# Power-Management.net
KiCad netlist of a schematic drawn in Altium Designer
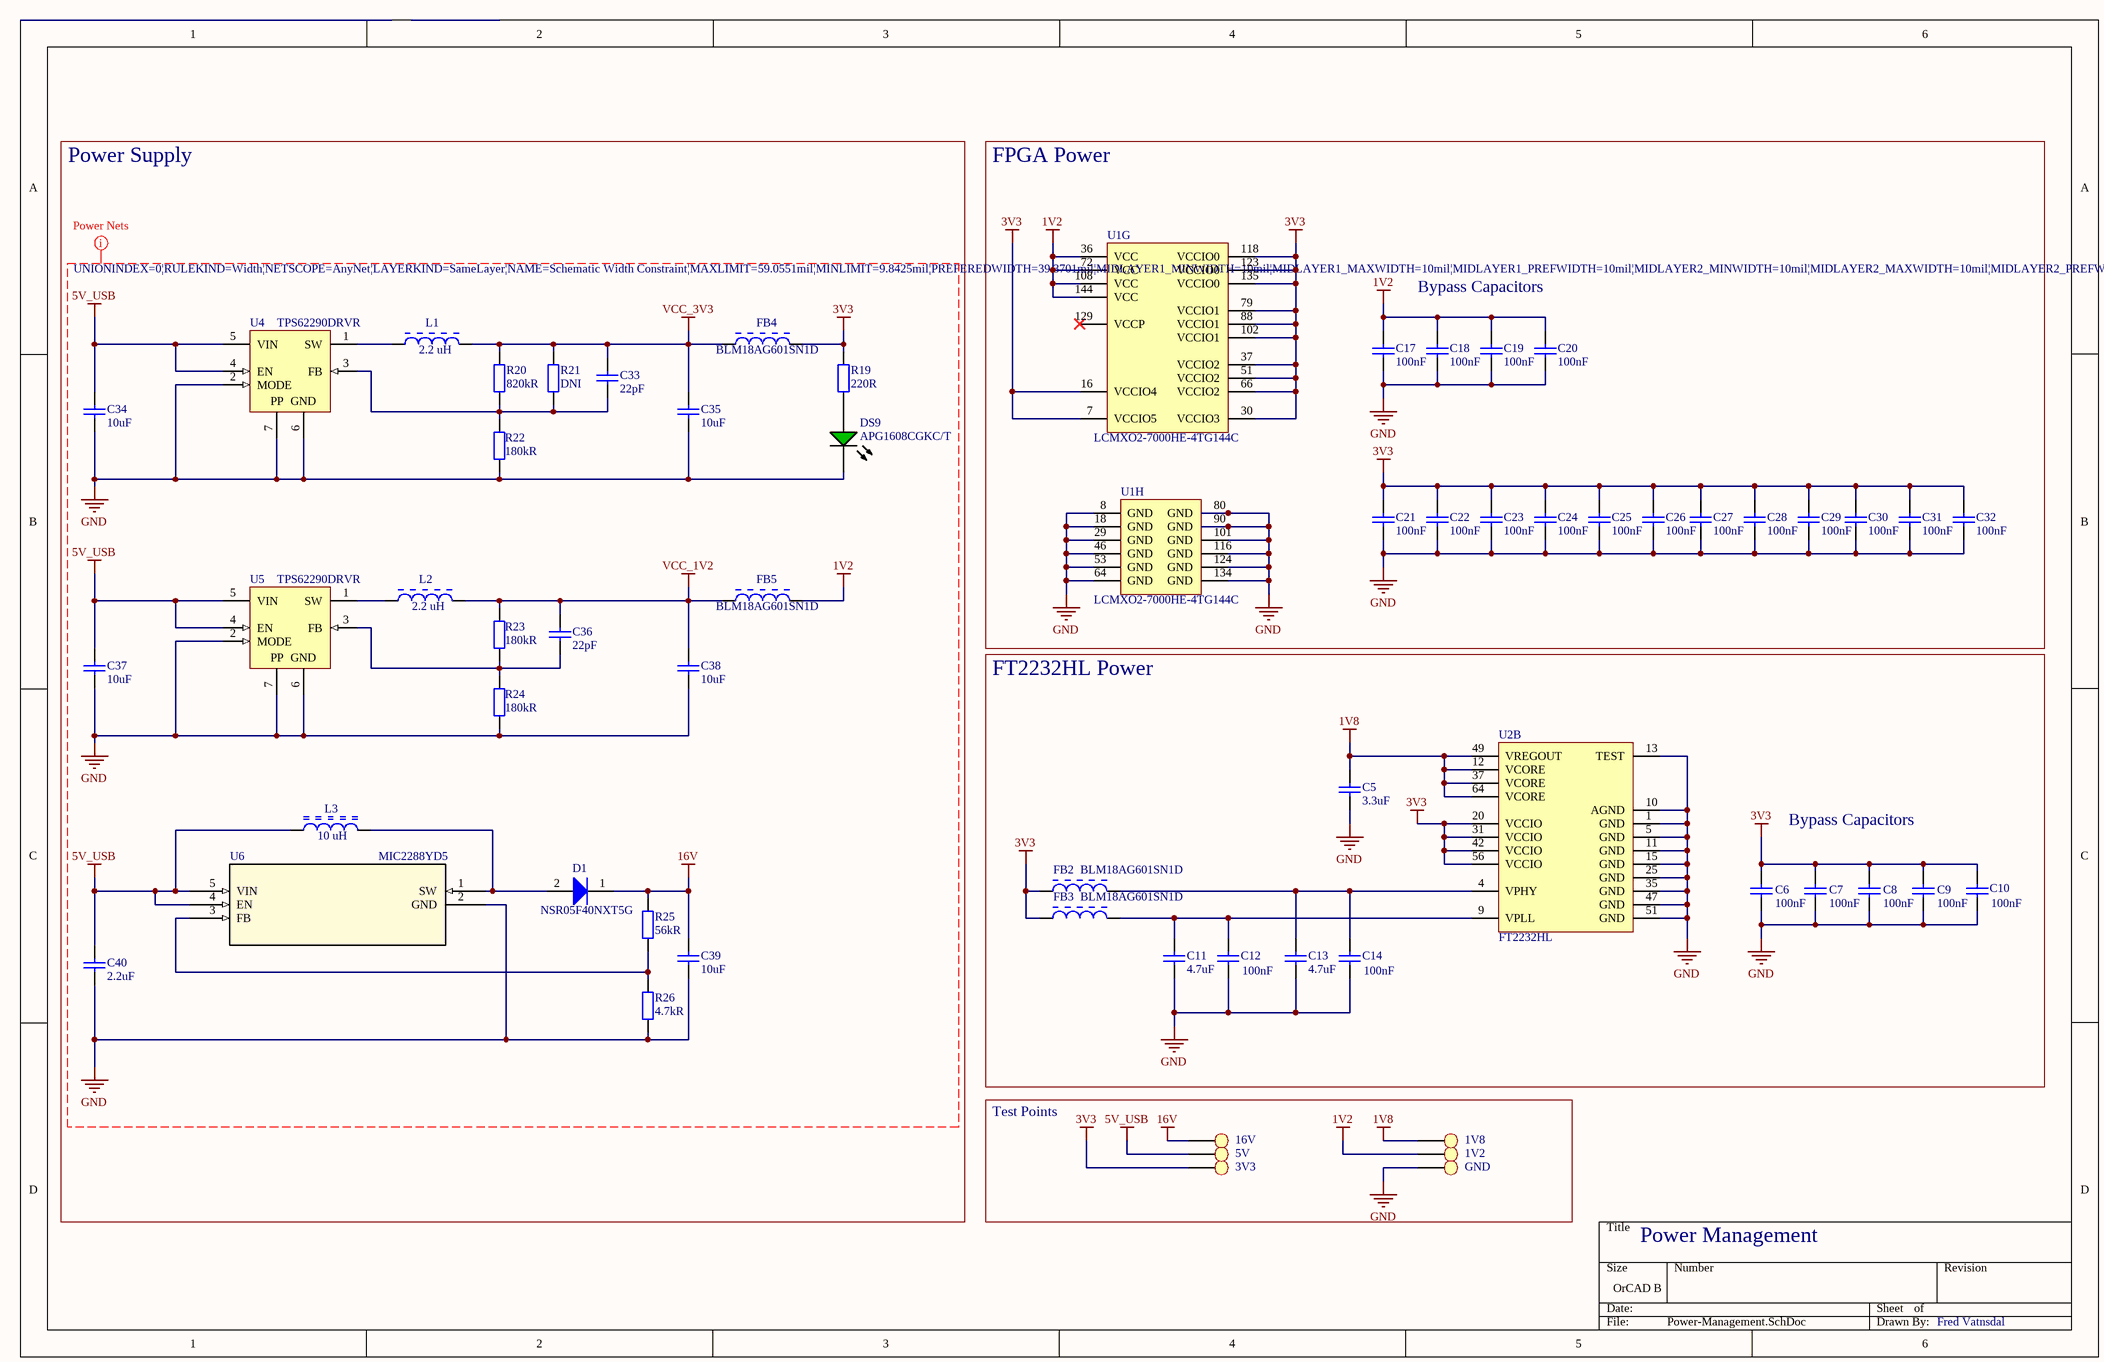
[diagram p0: Power-Management.SchDoc]

(export (version "E")
  (design (tool "Eeschema 10.0.6"))
  (components
    (comp (ref "1V2") (value "TP") (footprint "TP_0.75DIA") (libsource (lib "LCD-Controller") (part "TP")))
    (comp (ref "1V8") (value "TP") (footprint "TP_0.75DIA") (libsource (lib "LCD-Controller") (part "TP")))
    (comp (ref "3V3") (value "TP") (footprint "TP_0.75DIA") (libsource (lib "LCD-Controller") (part "TP")))
    (comp (ref "5V") (value "TP") (footprint "TP_0.75DIA") (libsource (lib "LCD-Controller") (part "TP")))
    (comp (ref "16V") (value "TP") (footprint "TP_0.75DIA") (libsource (lib "LCD-Controller") (part "TP")))
    (comp (ref "C5")
      (value "CAP 3.3uF 10V 0603(1608)")
      (footprint "CAP_0603_imperial")
      (description "CAP CER 3.3UF 6.3V X5R 0603")
      (fields
        (field (name "TOLERANCE") "20%")
        (field (name "MANUFACTURER") "KEMET")
        (field (name "CAPACITANCE") "3.3uF")
      )
      (libsource (lib "LCD-Controller") (part "C0603C335M9PACTU"))
    )
    (comp (ref "C6")
      (value "C0402C104K4RAC-TU")
      (footprint "CAP_0402_imperial")
      (description "CAP CER 0.1UF 16V X7R 0402")
      (fields
        (field (name "MANUFACTURER") "KEMET")
        (field (name "TOLERANCE") "10%")
        (field (name "CAPACITANCE") "100nF")
      )
      (libsource (lib "LCD-Controller") (part "C0402C104K4RAC-TU"))
    )
    (comp (ref "C7")
      (value "C0402C104K4RACTU")
      (footprint "CAP_0402_imperial")
      (description "CAP CER 0.1UF 16V X7R 0402")
      (fields
        (field (name "MANUFACTURER") "KEMET")
        (field (name "MANUFACTURER PART NUMBER") "C0402C104K4RAC-TU")
        (field (name "CAPACITANCE") "100nF")
      )
      (libsource (lib "LCD-Controller") (part "C0402C104K4RAC-TU"))
    )
    (comp (ref "C8")
      (value "C0402C104K4RACTU")
      (footprint "CAP_0402_imperial")
      (description "CAP CER 0.1UF 16V X7R 0402")
      (fields
        (field (name "MANUFACTURER") "KEMET")
        (field (name "MANUFACTURER PART NUMBER") "C0402C104K4RAC-TU")
        (field (name "CAPACITANCE") "100nF")
      )
      (libsource (lib "LCD-Controller") (part "C0402C104K4RAC-TU"))
    )
    (comp (ref "C9")
      (value "C0402C104K4RACTU")
      (footprint "CAP_0402_imperial")
      (description "CAP CER 0.1UF 16V X7R 0402")
      (fields
        (field (name "MANUFACTURER") "KEMET")
        (field (name "MANUFACTURER PART NUMBER") "C0402C104K4RAC-TU")
        (field (name "CAPACITANCE") "100nF")
      )
      (libsource (lib "LCD-Controller") (part "C0402C104K4RAC-TU"))
    )
    (comp (ref "C10")
      (value "C0402C104K4RACTU")
      (footprint "CAP_0402_imperial")
      (description "CAP CER 0.1UF 16V X7R 0402")
      (fields
        (field (name "MANUFACTURER") "KEMET")
        (field (name "MANUFACTURER PART NUMBER") "C0402C104K4RAC-TU")
        (field (name "CAPACITANCE") "100nF")
      )
      (libsource (lib "LCD-Controller") (part "C0402C104K4RAC-TU"))
    )
    (comp (ref "C11")
      (value "CAP 4.7uF 10V 0805(2012)")
      (footprint "CAP_0603_imperial")
      (fields
        (field (name "TOLERANCE") "10%")
        (field (name "MANUFACTURER") "Murata")
        (field (name "MANUFACTURER PART NUMBER") "GRM188R61E475KE11D")
        (field (name "CAPACITANCE") "4.7uF")
      )
      (libsource (lib "LCD-Controller") (part "GRM188R61E475KE11D"))
    )
    (comp (ref "C12")
      (value "C0402C104K4RACTU")
      (footprint "CAP_0402_imperial")
      (description "CAP CER 0.1UF 16V X7R 0402")
      (fields
        (field (name "MANUFACTURER") "KEMET")
        (field (name "MANUFACTURER PART NUMBER") "C0402C104K4RAC-TU")
        (field (name "CAPACITANCE") "100nF")
      )
      (libsource (lib "LCD-Controller") (part "C0402C104K4RAC-TU"))
    )
    (comp (ref "C13")
      (value "CAP 4.7uF 10V 0805(2012)")
      (footprint "CAP_0603_imperial")
      (fields
        (field (name "TOLERANCE") "10%")
        (field (name "MANUFACTURER") "Murata")
        (field (name "MANUFACTURER PART NUMBER") "GRM188R61E475KE11D")
        (field (name "CAPACITANCE") "4.7uF")
      )
      (libsource (lib "LCD-Controller") (part "GRM188R61E475KE11D"))
    )
    (comp (ref "C14")
      (value "C0402C104K4RACTU")
      (footprint "CAP_0402_imperial")
      (description "CAP CER 0.1UF 16V X7R 0402")
      (fields
        (field (name "MANUFACTURER") "KEMET")
        (field (name "MANUFACTURER PART NUMBER") "C0402C104K4RAC-TU")
        (field (name "CAPACITANCE") "100nF")
      )
      (libsource (lib "LCD-Controller") (part "C0402C104K4RAC-TU"))
    )
    (comp (ref "C17")
      (value "C0402C104K4RACTU")
      (footprint "CAP_0402_imperial")
      (description "CAP CER 0.1UF 16V X7R 0402")
      (fields
        (field (name "MANUFACTURER") "KEMET")
        (field (name "MANUFACTURER PART NUMBER") "C0402C104K4RAC-TU")
        (field (name "CAPACITANCE") "100nF")
      )
      (libsource (lib "LCD-Controller") (part "C0402C104K4RAC-TU"))
    )
    (comp (ref "C18")
      (value "C0402C104K4RACTU")
      (footprint "CAP_0402_imperial")
      (description "CAP CER 0.1UF 16V X7R 0402")
      (fields
        (field (name "MANUFACTURER") "KEMET")
        (field (name "MANUFACTURER PART NUMBER") "C0402C104K4RAC-TU")
        (field (name "CAPACITANCE") "100nF")
      )
      (libsource (lib "LCD-Controller") (part "C0402C104K4RAC-TU"))
    )
    (comp (ref "C19")
      (value "C0402C104K4RACTU")
      (footprint "CAP_0402_imperial")
      (description "CAP CER 0.1UF 16V X7R 0402")
      (fields
        (field (name "MANUFACTURER") "KEMET")
        (field (name "MANUFACTURER PART NUMBER") "C0402C104K4RAC-TU")
        (field (name "CAPACITANCE") "100nF")
      )
      (libsource (lib "LCD-Controller") (part "C0402C104K4RAC-TU"))
    )
    (comp (ref "C20")
      (value "C0402C104K4RACTU")
      (footprint "CAP_0402_imperial")
      (description "CAP CER 0.1UF 16V X7R 0402")
      (fields
        (field (name "MANUFACTURER") "KEMET")
        (field (name "MANUFACTURER PART NUMBER") "C0402C104K4RAC-TU")
        (field (name "CAPACITANCE") "100nF")
      )
      (libsource (lib "LCD-Controller") (part "C0402C104K4RAC-TU"))
    )
    (comp (ref "C21")
      (value "C0402C104K4RACTU")
      (footprint "CAP_0402_imperial")
      (description "CAP CER 0.1UF 16V X7R 0402")
      (fields
        (field (name "MANUFACTURER") "KEMET")
        (field (name "MANUFACTURER PART NUMBER") "C0402C104K4RAC-TU")
        (field (name "CAPACITANCE") "100nF")
      )
      (libsource (lib "LCD-Controller") (part "C0402C104K4RAC-TU"))
    )
    (comp (ref "C22")
      (value "C0402C104K4RACTU")
      (footprint "CAP_0402_imperial")
      (description "CAP CER 0.1UF 16V X7R 0402")
      (fields
        (field (name "MANUFACTURER") "KEMET")
        (field (name "MANUFACTURER PART NUMBER") "C0402C104K4RAC-TU")
        (field (name "CAPACITANCE") "100nF")
      )
      (libsource (lib "LCD-Controller") (part "C0402C104K4RAC-TU"))
    )
    (comp (ref "C23")
      (value "C0402C104K4RACTU")
      (footprint "CAP_0402_imperial")
      (description "CAP CER 0.1UF 16V X7R 0402")
      (fields
        (field (name "MANUFACTURER") "KEMET")
        (field (name "MANUFACTURER PART NUMBER") "C0402C104K4RAC-TU")
        (field (name "CAPACITANCE") "100nF")
      )
      (libsource (lib "LCD-Controller") (part "C0402C104K4RAC-TU"))
    )
    (comp (ref "C24")
      (value "C0402C104K4RACTU")
      (footprint "CAP_0402_imperial")
      (description "CAP CER 0.1UF 16V X7R 0402")
      (fields
        (field (name "MANUFACTURER") "KEMET")
        (field (name "MANUFACTURER PART NUMBER") "C0402C104K4RAC-TU")
        (field (name "CAPACITANCE") "100nF")
      )
      (libsource (lib "LCD-Controller") (part "C0402C104K4RAC-TU"))
    )
    (comp (ref "C25")
      (value "C0402C104K4RACTU")
      (footprint "CAP_0402_imperial")
      (description "CAP CER 0.1UF 16V X7R 0402")
      (fields
        (field (name "MANUFACTURER") "KEMET")
        (field (name "MANUFACTURER PART NUMBER") "C0402C104K4RAC-TU")
        (field (name "CAPACITANCE") "100nF")
      )
      (libsource (lib "LCD-Controller") (part "C0402C104K4RAC-TU"))
    )
    (comp (ref "C26")
      (value "C0402C104K4RACTU")
      (footprint "CAP_0402_imperial")
      (description "CAP CER 0.1UF 16V X7R 0402")
      (fields
        (field (name "MANUFACTURER") "KEMET")
        (field (name "MANUFACTURER PART NUMBER") "C0402C104K4RAC-TU")
        (field (name "CAPACITANCE") "100nF")
      )
      (libsource (lib "LCD-Controller") (part "C0402C104K4RAC-TU"))
    )
    (comp (ref "C27")
      (value "C0402C104K4RACTU")
      (footprint "CAP_0402_imperial")
      (description "CAP CER 0.1UF 16V X7R 0402")
      (fields
        (field (name "MANUFACTURER") "KEMET")
        (field (name "MANUFACTURER PART NUMBER") "C0402C104K4RAC-TU")
        (field (name "CAPACITANCE") "100nF")
      )
      (libsource (lib "LCD-Controller") (part "C0402C104K4RAC-TU"))
    )
    (comp (ref "C28")
      (value "C0402C104K4RACTU")
      (footprint "CAP_0402_imperial")
      (description "CAP CER 0.1UF 16V X7R 0402")
      (fields
        (field (name "MANUFACTURER") "KEMET")
        (field (name "MANUFACTURER PART NUMBER") "C0402C104K4RAC-TU")
        (field (name "CAPACITANCE") "100nF")
      )
      (libsource (lib "LCD-Controller") (part "C0402C104K4RAC-TU"))
    )
    (comp (ref "C29")
      (value "C0402C104K4RACTU")
      (footprint "CAP_0402_imperial")
      (description "CAP CER 0.1UF 16V X7R 0402")
      (fields
        (field (name "MANUFACTURER") "KEMET")
        (field (name "MANUFACTURER PART NUMBER") "C0402C104K4RAC-TU")
        (field (name "CAPACITANCE") "100nF")
      )
      (libsource (lib "LCD-Controller") (part "C0402C104K4RAC-TU"))
    )
    (comp (ref "C30")
      (value "C0402C104K4RACTU")
      (footprint "CAP_0402_imperial")
      (description "CAP CER 0.1UF 16V X7R 0402")
      (fields
        (field (name "MANUFACTURER") "KEMET")
        (field (name "MANUFACTURER PART NUMBER") "C0402C104K4RAC-TU")
        (field (name "CAPACITANCE") "100nF")
      )
      (libsource (lib "LCD-Controller") (part "C0402C104K4RAC-TU"))
    )
    (comp (ref "C31")
      (value "C0402C104K4RACTU")
      (footprint "CAP_0402_imperial")
      (description "CAP CER 0.1UF 16V X7R 0402")
      (fields
        (field (name "MANUFACTURER") "KEMET")
        (field (name "MANUFACTURER PART NUMBER") "C0402C104K4RAC-TU")
        (field (name "CAPACITANCE") "100nF")
      )
      (libsource (lib "LCD-Controller") (part "C0402C104K4RAC-TU"))
    )
    (comp (ref "C32")
      (value "C0402C104K4RACTU")
      (footprint "CAP_0402_imperial")
      (description "CAP CER 0.1UF 16V X7R 0402")
      (fields
        (field (name "MANUFACTURER") "KEMET")
        (field (name "MANUFACTURER PART NUMBER") "C0402C104K4RAC-TU")
        (field (name "CAPACITANCE") "100nF")
      )
      (libsource (lib "LCD-Controller") (part "C0402C104K4RAC-TU"))
    )
    (comp (ref "C33")
      (value "06035A220JAT2A")
      (footprint "CAP_0603_imperial")
      (description "CAP CER 22PF 50V C0G 0603")
      (fields
        (field (name "MANUFACTURER") "TDK")
        (field (name "CAPACITANCE") "22pF")
        (field (name "MANUFACTURER PART NUMBER") "C1608C0G1H220J080AA")
      )
      (libsource (lib "LCD-Controller") (part "C1608C0G1H220J080AA"))
    )
    (comp (ref "C34")
      (value "GRM31CR61E106KA12L")
      (footprint "CAP_0603_imperial")
      (description "CAP CER 10UF 10V X5R 0603")
      (fields
        (field (name "MANUFACTURER") "Taiyo Yuden")
        (field (name "TOLERANCE") "20%")
        (field (name "CAPACITANCE") "10uF")
      )
      (libsource (lib "LCD-Controller") (part "LMK107BJ106MALTD"))
    )
    (comp (ref "C35")
      (value "GRM31CR61E106KA12L")
      (footprint "CAP_0603_imperial")
      (description "CAP CER 10UF 10V X5R 0603")
      (fields
        (field (name "MANUFACTURER") "Taiyo Yuden")
        (field (name "TOLERANCE") "20%")
        (field (name "CAPACITANCE") "10uF")
      )
      (libsource (lib "LCD-Controller") (part "LMK107BJ106MALTD"))
    )
    (comp (ref "C36")
      (value "06035A220JAT2A")
      (footprint "CAP_0603_imperial")
      (description "CAP CER 22PF 50V C0G 0603")
      (fields
        (field (name "MANUFACTURER") "TDK")
        (field (name "CAPACITANCE") "22pF")
        (field (name "MANUFACTURER PART NUMBER") "C1608C0G1H220J080AA")
      )
      (libsource (lib "LCD-Controller") (part "C1608C0G1H220J080AA"))
    )
    (comp (ref "C37")
      (value "GRM31CR61E106KA12L")
      (footprint "CAP_0603_imperial")
      (description "CAP CER 10UF 10V X5R 0603")
      (fields
        (field (name "MANUFACTURER") "Taiyo Yuden")
        (field (name "TOLERANCE") "20%")
        (field (name "CAPACITANCE") "10uF")
      )
      (libsource (lib "LCD-Controller") (part "LMK107BJ106MALTD"))
    )
    (comp (ref "C38")
      (value "GRM31CR61E106KA12L")
      (footprint "CAP_0603_imperial")
      (description "CAP CER 10UF 10V X5R 0603")
      (fields
        (field (name "MANUFACTURER") "Taiyo Yuden")
        (field (name "TOLERANCE") "20%")
        (field (name "CAPACITANCE") "10uF")
      )
      (libsource (lib "LCD-Controller") (part "LMK107BJ106MALTD"))
    )
    (comp (ref "C39")
      (value "GRM31CR61E106KA12L")
      (footprint "CAP_0603_imperial")
      (description "CAP CER 10UF 10V X5R 0603")
      (fields
        (field (name "MANUFACTURER") "Taiyo Yuden")
        (field (name "TOLERANCE") "20%")
        (field (name "CAPACITANCE") "10uF")
      )
      (libsource (lib "LCD-Controller") (part "LMK107BJ106MALTD"))
    )
    (comp (ref "C40")
      (value "GRM188R61A225KE34x")
      (footprint "CAP_0603_imperial")
      (description "CAP CER 2.2UF 10V X7R 0603")
      (fields
        (field (name "CAPACITANCE") "2.2uF")
        (field (name "TOLERANCE") "10%")
        (field (name "MANUFACTURER") "Murata")
      )
      (libsource (lib "LCD-Controller") (part "GRM188R71A225KE15D"))
    )
    (comp (ref "D1")
      (value "NSR05F40NXT5G")
      (footprint "ONSC-DSN-2-152AC-01_V")
      (description "Schottky Barrier Diode, 2-Pin DSN, Pb-Free, Tape and Reel")
      (fields (field (name "MANUFACTURER") "On Semiconductor"))
      (libsource (lib "Altium Content Vault") (part "ONSC-D-K1A2-2"))
    )
    (comp (ref "DS9")
      (value "APG1608CGKC/T")
      (footprint "KING-LED0603-25-GREEN_V")
      (description "LED, SMT, 0603(1608), 0.25mm Thickness, Green")
      (libsource (lib "Altium Content Vault") (part "KING-LED_GREEN_A1K2-2"))
    )
    (comp (ref "FB2")
      (value "BLM18AG601SN1D")
      (footprint "MURA-BLM18-F-H1-CHIP-2_V")
      (fields (field (name "MANUFACTURER") "Murata"))
      (libsource (lib "Altium Content Vault") (part "MURA-FB-2"))
    )
    (comp (ref "FB3")
      (value "BLM18AG601SN1D")
      (footprint "MURA-BLM18-F-H1-CHIP-2_V")
      (fields (field (name "MANUFACTURER") "Murata"))
      (libsource (lib "Altium Content Vault") (part "MURA-FB-2"))
    )
    (comp (ref "FB4")
      (value "BLM18AG601SN1D")
      (footprint "MURA-BLM18-F-H1-CHIP-2_V")
      (fields (field (name "MANUFACTURER") "Murata"))
      (libsource (lib "Altium Content Vault") (part "MURA-FB-2"))
    )
    (comp (ref "FB5")
      (value "BLM18AG601SN1D")
      (footprint "MURA-BLM18-F-H1-CHIP-2_V")
      (fields (field (name "MANUFACTURER") "Murata"))
      (libsource (lib "Altium Content Vault") (part "MURA-FB-2"))
    )
    (comp (ref "GND") (value "TP") (footprint "TP_0.75DIA") (libsource (lib "LCD-Controller") (part "TP")))
    (comp (ref "L1")
      (value "SRN3015-2R2M")
      (footprint "BOUR-SRN3015-2_V")
      (fields (field (name "MANUFACTURER") "Bourns") (field (name "INDUCTANCE") "2.2 uH"))
      (libsource (lib "Altium Content Vault") (part "BOUR-IND-2A"))
    )
    (comp (ref "L2")
      (value "SRN3015-2R2M")
      (footprint "BOUR-SRN3015-2_V")
      (fields (field (name "MANUFACTURER") "Bourns") (field (name "INDUCTANCE") "2.2 uH"))
      (libsource (lib "Altium Content Vault") (part "BOUR-IND-2A"))
    )
    (comp (ref "L3")
      (value "CM322522-100KL")
      (footprint "BOUR-CM322522_V")
      (description "Chip Inductor\r\n, 10 uH, +/- 10%, -40 to 125 degC, 1210 (3225 Metric), RoHS, Tape and Reel")
      (fields (field (name "INDUCTANCE") "10 uH"))
      (libsource (lib "") (part "BOUR-IND-2A_1"))
    )
    (comp (ref "R19")
      (value "220R 1% 0603(1608)")
      (footprint "RES_0603_imperial")
      (description "Res Thin Film 0603 220 Ohm 0.1% 1/10W ±25ppm/C Molded SMD Punched Carrier T/R")
      (fields
        (field (name "TOLERANCE") "0.1%")
        (field (name "MANUFACTURER") "Panasonic")
        (field (name "RESISTANCE") "220R")
      )
      (libsource (lib "LCD-Controller") (part "ERA-3AEB221V"))
    )
    (comp (ref "R20")
      (value "820K 1% 0603(1608)")
      (footprint "RES_0603_imperial")
      (description "RESISTOR, 0603, 0.1W, 1%, 820K")
      (fields
        (field (name "TOLERANCE") "1%")
        (field (name "MANUFACTURER") "Panasonic")
        (field (name "RESISTANCE") "820kR")
      )
      (libsource (lib "LCD-Controller") (part "ERJ-3EKF8203V"))
    )
    (comp (ref "R21")
      (value "820K 1% 0603(1608)")
      (footprint "RES_0603_imperial")
      (description "RESISTOR, 0603, 0.1W, 1%, 820K")
      (fields
        (field (name "TOLERANCE") "1%")
        (field (name "MANUFACTURER") "Panasonic")
        (field (name "RESISTANCE") "DNI")
      )
      (libsource (lib "LCD-Controller") (part "ERJ-3EKF8203V"))
    )
    (comp (ref "R22")
      (value "180K 1% 0603(1608)")
      (footprint "RES_0603_imperial")
      (description "RESISTOR, 0603, 180K, 0.1%, 0.1W")
      (fields
        (field (name "TOLERANCE") "0.1%")
        (field (name "MANUFACTURER") "Panasonic")
        (field (name "RESISTANCE") "180kR")
      )
      (libsource (lib "LCD-Controller") (part "ERA-3AEB184V"))
    )
    (comp (ref "R23")
      (value "180K 1% 0603(1608)")
      (footprint "RES_0603_imperial")
      (description "RESISTOR, 0603, 180K, 0.1%, 0.1W")
      (fields
        (field (name "TOLERANCE") "0.1%")
        (field (name "MANUFACTURER") "Panasonic")
        (field (name "RESISTANCE") "180kR")
      )
      (libsource (lib "LCD-Controller") (part "ERA-3AEB184V"))
    )
    (comp (ref "R24")
      (value "180K 1% 0603(1608)")
      (footprint "RES_0603_imperial")
      (description "RESISTOR, 0603, 180K, 0.1%, 0.1W")
      (fields
        (field (name "TOLERANCE") "0.1%")
        (field (name "MANUFACTURER") "Panasonic")
        (field (name "RESISTANCE") "180kR")
      )
      (libsource (lib "LCD-Controller") (part "ERA-3AEB184V"))
    )
    (comp (ref "R25")
      (value "56K 1% 0603(1608)")
      (footprint "RES_0603_imperial")
      (fields
        (field (name "TOLERANCE") "1%")
        (field (name "MANUFACTURER") "Panasonic")
        (field (name "MANUFACTURER PART NUMBER") "ERJ-3EKF5602V")
        (field (name "RESISTANCE") "56kR")
      )
      (libsource (lib "LCD-Controller") (part "ERJ-3EKF5602V"))
    )
    (comp (ref "R26")
      (value "4K7 1% 0603(1608)")
      (footprint "RES_0603_imperial")
      (description "Res Thin Film 0603 4.7K Ohm 0.1% 0.1W(1/10W) ±25ppm/C Molded SMD Automotive Punched T/R")
      (fields
        (field (name "TOLERANCE") "0.1%")
        (field (name "MANUFACTURER") "Panasonic")
        (field (name "RESISTANCE") "4.7kR")
      )
      (libsource (lib "LCD-Controller") (part "ERA-3AEB472V"))
    )
    (comp (ref "U1")
      (value "LCMXO2-7000HE-4TG144C")
      (footprint "TQFP144_L")
      (libsource (lib "Altium Content Vault") (part "PLD-LTMXO2-7000-TQ144"))
    )
    (comp (ref "U2")
      (value "FT2232HL")
      (footprint "FTDI-LQFP-64_L")
      (fields (field (name "MANUFACTURER") "FTDI"))
      (libsource (lib "Altium Content Vault") (part "FTDI-FT2232HL-LQFP-64"))
    )
    (comp (ref "U4")
      (value "TPS62290DRVR")
      (footprint "DRV6-1600X1000TP")
      (fields (field (name "MANUFACTURER") "Texas Instruments"))
      (libsource (lib "Altium Content Vault") (part "TI-TPS62290DRV6-1600X1000TP"))
    )
    (comp (ref "U5")
      (value "TPS62290DRVR")
      (footprint "DRV6-1600X1000TP")
      (fields (field (name "MANUFACTURER") "Texas Instruments"))
      (libsource (lib "Altium Content Vault") (part "TI-TPS62290DRV6-1600X1000TP"))
    )
    (comp (ref "U6")
      (value "MIC2288YD5")
      (footprint "TSOT-23-5_D5")
      (description "Imported")
      (fields (field (name "MANUFACTURER_PART_NUMBER") "mic2288yd5"))
      (libsource (lib "MIC2288") (part "MIC2288YD5"))
    )
  )
  (nets
    (net (code "1") (name "1V2") (class "Default")
      (node (ref "1V2") (pin "1") (pinfunction "1_1") (pintype "passive"))
      (node (ref "C17") (pin "1") (pinfunction "1_1") (pintype "passive"))
      (node (ref "C18") (pin "1") (pinfunction "1_1") (pintype "passive"))
      (node (ref "C19") (pin "1") (pinfunction "1_1") (pintype "passive"))
      (node (ref "C20") (pin "1") (pinfunction "1_1") (pintype "passive"))
      (node (ref "FB5") (pin "2") (pinfunction "2_2") (pintype "passive"))
      (node (ref "U1") (pin "108") (pinfunction "VCC_108") (pintype "power_in"))
      (node (ref "U1") (pin "144") (pinfunction "VCC_144") (pintype "power_in"))
      (node (ref "U1") (pin "36") (pinfunction "VCC_36") (pintype "power_in"))
      (node (ref "U1") (pin "72") (pinfunction "VCC_72") (pintype "power_in"))
    )
    (net (code "2") (name "1V8") (class "Default")
      (node (ref "1V8") (pin "1") (pinfunction "1_1") (pintype "passive"))
      (node (ref "C5") (pin "1") (pinfunction "1_1") (pintype "passive"))
      (node (ref "U2") (pin "12") (pinfunction "VCORE_12") (pintype "power_in"))
      (node (ref "U2") (pin "37") (pinfunction "VCORE_37") (pintype "power_in"))
      (node (ref "U2") (pin "49") (pinfunction "VREGOUT_49") (pintype "power_in"))
      (node (ref "U2") (pin "64") (pinfunction "VCORE_64") (pintype "power_in"))
    )
    (net (code "3") (name "3V3") (class "Default")
      (node (ref "3V3") (pin "1") (pinfunction "1_1") (pintype "passive"))
      (node (ref "C10") (pin "1") (pinfunction "1_1") (pintype "passive"))
      (node (ref "C21") (pin "1") (pinfunction "1_1") (pintype "passive"))
      (node (ref "C22") (pin "1") (pinfunction "1_1") (pintype "passive"))
      (node (ref "C23") (pin "1") (pinfunction "1_1") (pintype "passive"))
      (node (ref "C24") (pin "1") (pinfunction "1_1") (pintype "passive"))
      (node (ref "C25") (pin "1") (pinfunction "1_1") (pintype "passive"))
      (node (ref "C26") (pin "1") (pinfunction "1_1") (pintype "passive"))
      (node (ref "C27") (pin "1") (pinfunction "1_1") (pintype "passive"))
      (node (ref "C28") (pin "1") (pinfunction "1_1") (pintype "passive"))
      (node (ref "C29") (pin "1") (pinfunction "1_1") (pintype "passive"))
      (node (ref "C30") (pin "1") (pinfunction "1_1") (pintype "passive"))
      (node (ref "C31") (pin "1") (pinfunction "1_1") (pintype "passive"))
      (node (ref "C32") (pin "1") (pinfunction "1_1") (pintype "passive"))
      (node (ref "C6") (pin "1") (pinfunction "1_1") (pintype "passive"))
      (node (ref "C7") (pin "1") (pinfunction "1_1") (pintype "passive"))
      (node (ref "C8") (pin "1") (pinfunction "1_1") (pintype "passive"))
      (node (ref "C9") (pin "1") (pinfunction "1_1") (pintype "passive"))
      (node (ref "FB2") (pin "1") (pinfunction "1_1") (pintype "passive"))
      (node (ref "FB3") (pin "1") (pinfunction "1_1") (pintype "passive"))
      (node (ref "FB4") (pin "2") (pinfunction "2_2") (pintype "passive"))
      (node (ref "R19") (pin "2") (pinfunction "2_2") (pintype "passive"))
      (node (ref "U1") (pin "102") (pinfunction "VCCIO1_102") (pintype "power_in"))
      (node (ref "U1") (pin "118") (pinfunction "VCCIO0_118") (pintype "power_in"))
      (node (ref "U1") (pin "123") (pinfunction "VCCIO0_123") (pintype "power_in"))
      (node (ref "U1") (pin "135") (pinfunction "VCCIO0_135") (pintype "power_in"))
      (node (ref "U1") (pin "16") (pinfunction "VCCIO4_16") (pintype "power_in"))
      (node (ref "U1") (pin "30") (pinfunction "VCCIO3_30") (pintype "power_in"))
      (node (ref "U1") (pin "37") (pinfunction "VCCIO2_37") (pintype "power_in"))
      (node (ref "U1") (pin "51") (pinfunction "VCCIO2_51") (pintype "power_in"))
      (node (ref "U1") (pin "66") (pinfunction "VCCIO2_66") (pintype "power_in"))
      (node (ref "U1") (pin "7") (pinfunction "VCCIO5_7") (pintype "power_in"))
      (node (ref "U1") (pin "79") (pinfunction "VCCIO1_79") (pintype "power_in"))
      (node (ref "U1") (pin "88") (pinfunction "VCCIO1_88") (pintype "power_in"))
      (node (ref "U2") (pin "20") (pinfunction "VCCIO_20") (pintype "power_in"))
      (node (ref "U2") (pin "31") (pinfunction "VCCIO_31") (pintype "power_in"))
      (node (ref "U2") (pin "42") (pinfunction "VCCIO_42") (pintype "power_in"))
      (node (ref "U2") (pin "56") (pinfunction "VCCIO_56") (pintype "power_in"))
    )
    (net (code "4") (name "5V_USB") (class "Default")
      (node (ref "5V") (pin "1") (pinfunction "1_1") (pintype "passive"))
      (node (ref "C34") (pin "1") (pinfunction "1_1") (pintype "passive"))
      (node (ref "C37") (pin "1") (pinfunction "1_1") (pintype "passive"))
      (node (ref "C40") (pin "1") (pinfunction "1_1") (pintype "passive"))
      (node (ref "L3") (pin "1") (pinfunction "1_1") (pintype "passive"))
      (node (ref "U4") (pin "4") (pinfunction "EN_4") (pintype "input"))
      (node (ref "U4") (pin "5") (pinfunction "VIN_5") (pintype "power_in"))
      (node (ref "U5") (pin "4") (pinfunction "EN_4") (pintype "input"))
      (node (ref "U5") (pin "5") (pinfunction "VIN_5") (pintype "power_in"))
      (node (ref "U6") (pin "4") (pinfunction "EN_4") (pintype "input"))
      (node (ref "U6") (pin "5") (pinfunction "VIN_5") (pintype "input"))
    )
    (net (code "5") (name "16V") (class "Default")
      (node (ref "16V") (pin "1") (pinfunction "1_1") (pintype "passive"))
      (node (ref "C39") (pin "1") (pinfunction "1_1") (pintype "passive"))
      (node (ref "D1") (pin "1") (pinfunction "K_1") (pintype "passive"))
      (node (ref "R25") (pin "2") (pinfunction "2_2") (pintype "passive"))
    )
    (net (code "6") (name "GND") (class "Default")
      (node (ref "C10") (pin "2") (pinfunction "2_2") (pintype "passive"))
      (node (ref "C11") (pin "2") (pinfunction "2_2") (pintype "passive"))
      (node (ref "C12") (pin "2") (pinfunction "2_2") (pintype "passive"))
      (node (ref "C13") (pin "2") (pinfunction "2_2") (pintype "passive"))
      (node (ref "C14") (pin "2") (pinfunction "2_2") (pintype "passive"))
      (node (ref "C17") (pin "2") (pinfunction "2_2") (pintype "passive"))
      (node (ref "C18") (pin "2") (pinfunction "2_2") (pintype "passive"))
      (node (ref "C19") (pin "2") (pinfunction "2_2") (pintype "passive"))
      (node (ref "C20") (pin "2") (pinfunction "2_2") (pintype "passive"))
      (node (ref "C21") (pin "2") (pinfunction "2_2") (pintype "passive"))
      (node (ref "C22") (pin "2") (pinfunction "2_2") (pintype "passive"))
      (node (ref "C23") (pin "2") (pinfunction "2_2") (pintype "passive"))
      (node (ref "C24") (pin "2") (pinfunction "2_2") (pintype "passive"))
      (node (ref "C25") (pin "2") (pinfunction "2_2") (pintype "passive"))
      (node (ref "C26") (pin "2") (pinfunction "2_2") (pintype "passive"))
      (node (ref "C27") (pin "2") (pinfunction "2_2") (pintype "passive"))
      (node (ref "C28") (pin "2") (pinfunction "2_2") (pintype "passive"))
      (node (ref "C29") (pin "2") (pinfunction "2_2") (pintype "passive"))
      (node (ref "C30") (pin "2") (pinfunction "2_2") (pintype "passive"))
      (node (ref "C31") (pin "2") (pinfunction "2_2") (pintype "passive"))
      (node (ref "C32") (pin "2") (pinfunction "2_2") (pintype "passive"))
      (node (ref "C34") (pin "2") (pinfunction "2_2") (pintype "passive"))
      (node (ref "C35") (pin "2") (pinfunction "2_2") (pintype "passive"))
      (node (ref "C37") (pin "2") (pinfunction "2_2") (pintype "passive"))
      (node (ref "C38") (pin "2") (pinfunction "2_2") (pintype "passive"))
      (node (ref "C39") (pin "2") (pinfunction "2_2") (pintype "passive"))
      (node (ref "C40") (pin "2") (pinfunction "2_2") (pintype "passive"))
      (node (ref "C5") (pin "2") (pinfunction "2_2") (pintype "passive"))
      (node (ref "C6") (pin "2") (pinfunction "2_2") (pintype "passive"))
      (node (ref "C7") (pin "2") (pinfunction "2_2") (pintype "passive"))
      (node (ref "C8") (pin "2") (pinfunction "2_2") (pintype "passive"))
      (node (ref "C9") (pin "2") (pinfunction "2_2") (pintype "passive"))
      (node (ref "DS9") (pin "2") (pinfunction "K_2") (pintype "passive"))
      (node (ref "GND") (pin "1") (pinfunction "1_1") (pintype "passive"))
      (node (ref "R22") (pin "1") (pinfunction "1_1") (pintype "passive"))
      (node (ref "R24") (pin "1") (pinfunction "1_1") (pintype "passive"))
      (node (ref "R26") (pin "1") (pinfunction "1_1") (pintype "passive"))
      (node (ref "U1") (pin "101") (pinfunction "GND_101") (pintype "power_in"))
      (node (ref "U1") (pin "116") (pinfunction "GND_116") (pintype "power_in"))
      (node (ref "U1") (pin "124") (pinfunction "GND_124") (pintype "power_in"))
      (node (ref "U1") (pin "134") (pinfunction "GND_134") (pintype "power_in"))
      (node (ref "U1") (pin "18") (pinfunction "GND_18") (pintype "power_in"))
      (node (ref "U1") (pin "29") (pinfunction "GND_29") (pintype "power_in"))
      (node (ref "U1") (pin "46") (pinfunction "GND_46") (pintype "power_in"))
      (node (ref "U1") (pin "53") (pinfunction "GND_53") (pintype "power_in"))
      (node (ref "U1") (pin "64") (pinfunction "GND_64") (pintype "power_in"))
      (node (ref "U1") (pin "8") (pinfunction "GND_8") (pintype "power_in"))
      (node (ref "U1") (pin "80") (pinfunction "GND_80") (pintype "power_in"))
      (node (ref "U1") (pin "90") (pinfunction "GND_90") (pintype "power_in"))
      (node (ref "U2") (pin "1") (pinfunction "GND_1") (pintype "power_in"))
      (node (ref "U2") (pin "10") (pinfunction "AGND_10") (pintype "power_in"))
      (node (ref "U2") (pin "11") (pinfunction "GND_11") (pintype "power_in"))
      (node (ref "U2") (pin "13") (pinfunction "TEST_13") (pintype "passive"))
      (node (ref "U2") (pin "15") (pinfunction "GND_15") (pintype "power_in"))
      (node (ref "U2") (pin "25") (pinfunction "GND_25") (pintype "power_in"))
      (node (ref "U2") (pin "35") (pinfunction "GND_35") (pintype "power_in"))
      (node (ref "U2") (pin "47") (pinfunction "GND_47") (pintype "power_in"))
      (node (ref "U2") (pin "5") (pinfunction "GND_5") (pintype "power_in"))
      (node (ref "U2") (pin "51") (pinfunction "GND_51") (pintype "power_in"))
      (node (ref "U4") (pin "2") (pinfunction "MODE_2") (pintype "input"))
      (node (ref "U4") (pin "6") (pinfunction "GND_6") (pintype "power_in"))
      (node (ref "U4") (pin "7") (pinfunction "PP_7") (pintype "power_in"))
      (node (ref "U5") (pin "2") (pinfunction "MODE_2") (pintype "input"))
      (node (ref "U5") (pin "6") (pinfunction "GND_6") (pintype "power_in"))
      (node (ref "U5") (pin "7") (pinfunction "PP_7") (pintype "power_in"))
      (node (ref "U6") (pin "2") (pinfunction "GND_2") (pintype "power_in"))
    )
    (net (code "7") (name "Net-(D1-A)") (class "Default")
      (node (ref "D1") (pin "2") (pinfunction "A_2") (pintype "passive"))
      (node (ref "L3") (pin "2") (pinfunction "2_2") (pintype "passive"))
      (node (ref "U6") (pin "1") (pinfunction "SW_1") (pintype "input"))
    )
    (net (code "8") (name "Net-(DS9-A)") (class "Default")
      (node (ref "DS9") (pin "1") (pinfunction "A_1") (pintype "passive"))
      (node (ref "R19") (pin "1") (pinfunction "1_1") (pintype "passive"))
    )
    (net (code "9") (name "Net-(U2B-VPHY)") (class "Default")
      (node (ref "C13") (pin "1") (pinfunction "1_1") (pintype "passive"))
      (node (ref "C14") (pin "1") (pinfunction "1_1") (pintype "passive"))
      (node (ref "FB2") (pin "2") (pinfunction "2_2") (pintype "passive"))
      (node (ref "U2") (pin "4") (pinfunction "VPHY_4") (pintype "power_in"))
    )
    (net (code "10") (name "Net-(U2B-VPLL)") (class "Default")
      (node (ref "C11") (pin "1") (pinfunction "1_1") (pintype "passive"))
      (node (ref "C12") (pin "1") (pinfunction "1_1") (pintype "passive"))
      (node (ref "FB3") (pin "2") (pinfunction "2_2") (pintype "passive"))
      (node (ref "U2") (pin "9") (pinfunction "VPLL_9") (pintype "power_in"))
    )
    (net (code "11") (name "Net-(U4-FB)") (class "Default")
      (node (ref "C33") (pin "2") (pinfunction "2_2") (pintype "passive"))
      (node (ref "R20") (pin "1") (pinfunction "1_1") (pintype "passive"))
      (node (ref "R21") (pin "1") (pinfunction "1_1") (pintype "passive"))
      (node (ref "R22") (pin "2") (pinfunction "2_2") (pintype "passive"))
      (node (ref "U4") (pin "3") (pinfunction "FB_3") (pintype "input"))
    )
    (net (code "12") (name "Net-(U4-SW)") (class "Default")
      (node (ref "L1") (pin "1") (pinfunction "1_1") (pintype "passive"))
      (node (ref "U4") (pin "1") (pinfunction "SW_1") (pintype "power_in"))
    )
    (net (code "13") (name "Net-(U5-FB)") (class "Default")
      (node (ref "C36") (pin "2") (pinfunction "2_2") (pintype "passive"))
      (node (ref "R23") (pin "1") (pinfunction "1_1") (pintype "passive"))
      (node (ref "R24") (pin "2") (pinfunction "2_2") (pintype "passive"))
      (node (ref "U5") (pin "3") (pinfunction "FB_3") (pintype "input"))
    )
    (net (code "14") (name "Net-(U5-SW)") (class "Default")
      (node (ref "L2") (pin "1") (pinfunction "1_1") (pintype "passive"))
      (node (ref "U5") (pin "1") (pinfunction "SW_1") (pintype "power_in"))
    )
    (net (code "15") (name "Net-(U6-FB)") (class "Default")
      (node (ref "R25") (pin "1") (pinfunction "1_1") (pintype "passive"))
      (node (ref "R26") (pin "2") (pinfunction "2_2") (pintype "passive"))
      (node (ref "U6") (pin "3") (pinfunction "FB_3") (pintype "input"))
    )
    (net (code "16") (name "VCC_1V2") (class "Default")
      (node (ref "C36") (pin "1") (pinfunction "1_1") (pintype "passive"))
      (node (ref "C38") (pin "1") (pinfunction "1_1") (pintype "passive"))
      (node (ref "FB5") (pin "1") (pinfunction "1_1") (pintype "passive"))
      (node (ref "L2") (pin "2") (pinfunction "2_2") (pintype "passive"))
      (node (ref "R23") (pin "2") (pinfunction "2_2") (pintype "passive"))
    )
    (net (code "17") (name "VCC_3V3") (class "Default")
      (node (ref "C33") (pin "1") (pinfunction "1_1") (pintype "passive"))
      (node (ref "C35") (pin "1") (pinfunction "1_1") (pintype "passive"))
      (node (ref "FB4") (pin "1") (pinfunction "1_1") (pintype "passive"))
      (node (ref "L1") (pin "2") (pinfunction "2_2") (pintype "passive"))
      (node (ref "R20") (pin "2") (pinfunction "2_2") (pintype "passive"))
      (node (ref "R21") (pin "2") (pinfunction "2_2") (pintype "passive"))
    )
    (net (code "18") (name "unconnected-(U1G-VCCP-Pad129)") (class "Default")
      (node (ref "U1") (pin "129") (pinfunction "VCCP_129") (pintype "power_in+no_connect"))
    )
  )
)
